# RPiHeatingArduinoOilSensorTCP-IO.net
KiCad netlist of a schematic drawn in EAGLE
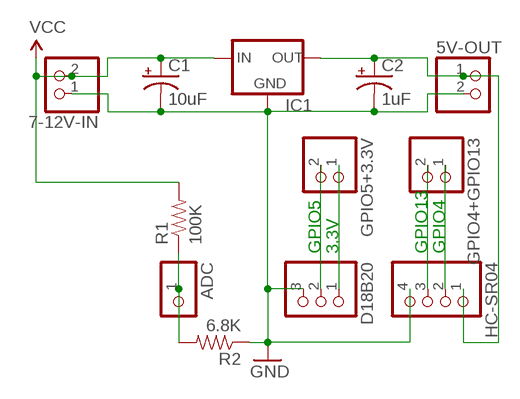
[diagram p0: schematic, sheet 1]

(export (version "E")
  (design (tool "Eeschema 10.0.6"))
  (components
    (comp (ref "5V-OUT")
      (value "PINHD-1X2")
      (footprint "eagle-import:1X02")
      (libsource (lib "eagle-import") (part "PINHD-1X2"))
    )
    (comp (ref "7-12V-IN")
      (value "PINHD-1X2")
      (footprint "eagle-import:1X02")
      (libsource (lib "eagle-import") (part "PINHD-1X2"))
    )
    (comp (ref "ADC")
      (value "PINHD-1X1")
      (footprint "eagle-import:1X01")
      (libsource (lib "eagle-import") (part "PINHD-1X1"))
    )
    (comp (ref "C1")
      (value "10uF")
      (footprint "eagle-import:CPOL-RADIAL-10UF-25V")
      (libsource (lib "eagle-import") (part "CAP_POLPTH2"))
    )
    (comp (ref "C2")
      (value "1uF")
      (footprint "eagle-import:CPOL-RADIAL-10UF-25V")
      (libsource (lib "eagle-import") (part "CAP_POLPTH2"))
    )
    (comp (ref "D18B20")
      (value "PINHD-1X3")
      (footprint "eagle-import:1X03")
      (libsource (lib "eagle-import") (part "PINHD-1X3"))
    )
    (comp (ref "GPIO4+GPIO13")
      (value "PINHD-1X2")
      (footprint "eagle-import:1X02")
      (libsource (lib "eagle-import") (part "PINHD-1X2"))
    )
    (comp (ref "GPIO5+3.3V")
      (value "PINHD-1X2")
      (footprint "eagle-import:1X02")
      (libsource (lib "eagle-import") (part "PINHD-1X2"))
    )
    (comp (ref "HC-SR04")
      (value "PINHD-1X4")
      (footprint "eagle-import:1X04")
      (libsource (lib "eagle-import") (part "PINHD-1X4"))
    )
    (comp (ref "IC1")
      (value "78XXL")
      (footprint "eagle-import:78XXL")
      (libsource (lib "eagle-import") (part "78XXL"))
    )
    (comp (ref "R1")
      (value "100K")
      (footprint "eagle-import:AXIAL-0.4")
      (libsource (lib "eagle-import") (part "RESISTORPTH-1/4W"))
    )
    (comp (ref "R2")
      (value "6.8K")
      (footprint "eagle-import:AXIAL-0.4")
      (libsource (lib "eagle-import") (part "RESISTORPTH-1/4W"))
    )
  )
  (nets
    (net (code "1") (name "GND") (class "Default")
      (node (ref "5V-OUT") (pin "2") (pinfunction "2_2") (pintype "passive"))
      (node (ref "7-12V-IN") (pin "1") (pinfunction "1_1") (pintype "passive"))
      (node (ref "C1") (pin "2") (pinfunction "-_2") (pintype "passive"))
      (node (ref "C2") (pin "2") (pinfunction "-_2") (pintype "passive"))
      (node (ref "D18B20") (pin "3") (pinfunction "3_3") (pintype "passive"))
      (node (ref "HC-SR04") (pin "4") (pinfunction "4_4") (pintype "passive"))
      (node (ref "IC1") (pin "GND") (pinfunction "GND_GND") (pintype "input"))
      (node (ref "R2") (pin "P$1") (pinfunction "1_P$1") (pintype "passive"))
    )
    (net (code "2") (name "Net-(C2-+)") (class "Default")
      (node (ref "5V-OUT") (pin "1") (pinfunction "1_1") (pintype "passive"))
      (node (ref "C2") (pin "1") (pinfunction "+_1") (pintype "passive"))
      (node (ref "HC-SR04") (pin "1") (pinfunction "1_1") (pintype "passive"))
      (node (ref "IC1") (pin "OUT") (pinfunction "OUT_OUT") (pintype "passive"))
    )
    (net (code "3") (name "Net-(D18B20-Pad1)") (class "Default")
      (node (ref "D18B20") (pin "1") (pinfunction "1_1") (pintype "passive"))
      (node (ref "GPIO5+3.3V") (pin "1") (pinfunction "1_1") (pintype "passive"))
    )
    (net (code "4") (name "Net-(D18B20-Pad2)") (class "Default")
      (node (ref "D18B20") (pin "2") (pinfunction "2_2") (pintype "passive"))
      (node (ref "GPIO5+3.3V") (pin "2") (pinfunction "2_2") (pintype "passive"))
    )
    (net (code "5") (name "Net-(GPIO4+GPIO13-Pad1)") (class "Default")
      (node (ref "GPIO4+GPIO13") (pin "1") (pinfunction "1_1") (pintype "passive"))
      (node (ref "HC-SR04") (pin "2") (pinfunction "2_2") (pintype "passive"))
    )
    (net (code "6") (name "Net-(GPIO4+GPIO13-Pad2)") (class "Default")
      (node (ref "GPIO4+GPIO13") (pin "2") (pinfunction "2_2") (pintype "passive"))
      (node (ref "HC-SR04") (pin "3") (pinfunction "3_3") (pintype "passive"))
    )
    (net (code "7") (name "Net-(R1-1)") (class "Default")
      (node (ref "ADC") (pin "1") (pinfunction "1_1") (pintype "passive"))
      (node (ref "R1") (pin "P$1") (pinfunction "1_P$1") (pintype "passive"))
      (node (ref "R2") (pin "P$2") (pinfunction "2_P$2") (pintype "passive"))
    )
    (net (code "8") (name "VCC") (class "Default")
      (node (ref "7-12V-IN") (pin "2") (pinfunction "2_2") (pintype "passive"))
      (node (ref "C1") (pin "1") (pinfunction "+_1") (pintype "passive"))
      (node (ref "IC1") (pin "IN") (pinfunction "IN_IN") (pintype "input"))
      (node (ref "R1") (pin "P$2") (pinfunction "2_P$2") (pintype "passive"))
    )
  )
)
